# MCU1.net
KiCad netlist of a schematic drawn in Altium Designer
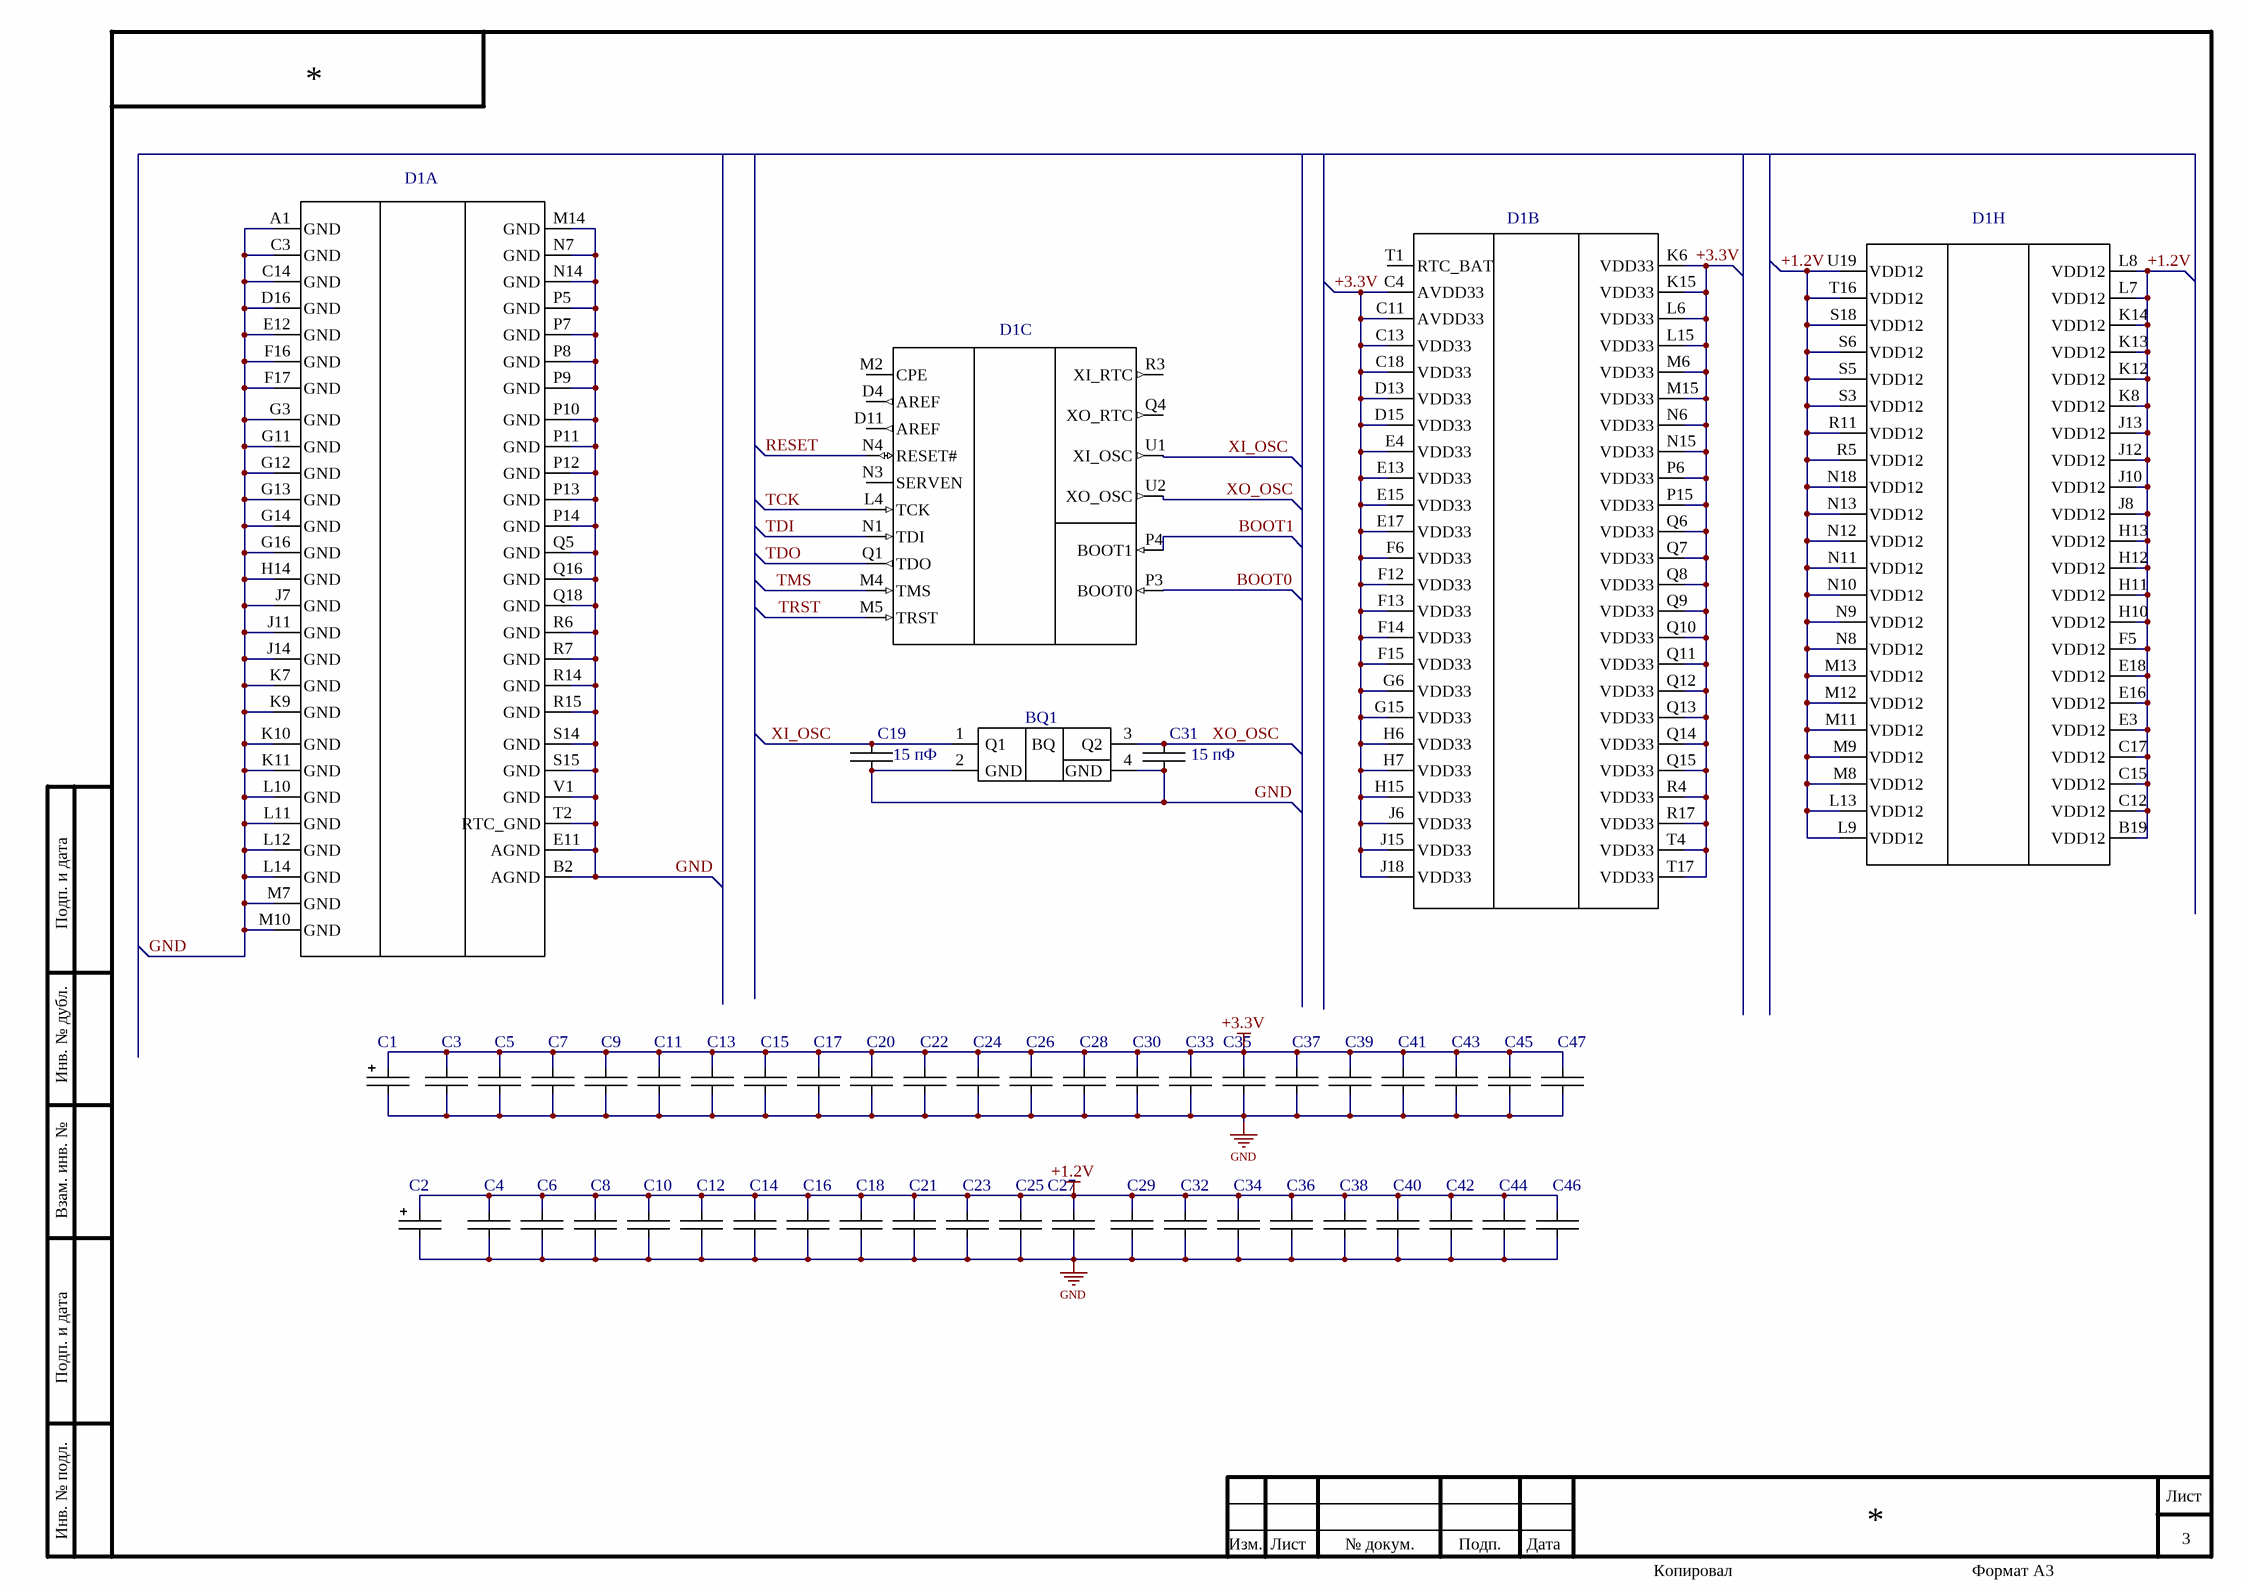
[diagram p0: MCU1.SchDoc]

(export (version "E")
  (design (tool "Eeschema 10.0.6"))
  (components
    (comp (ref "BQ1")
      (value "Резонатор РК463-5ДС-16,0М")
      (footprint "RK463_BQ_RK-463(Primary)")
      (description "Кварцевый резонатор")
      (libsource (lib "Блок вычислительный") (part "РК463-5ДС"))
    )
    (comp (ref "C1")
      (value "22 мкФ")
      (footprint "К53-67")
      (description "Оксидно-полупроводниковый танталовый чип-конденсатор серии К53-68")
      (fields (field (name "PARTNUMBER") "К53-67 \"*\"-* В-* мкФ ±*%"))
      (libsource (lib "Блок вычислительный") (part "К53-67"))
    )
    (comp (ref "C2")
      (value "22 мкФ")
      (footprint "К53-67")
      (description "Оксидно-полупроводниковый танталовый чип-конденсатор серии К53-68")
      (fields (field (name "PARTNUMBER") "К53-67 \"*\"-* В-* мкФ ±*%"))
      (libsource (lib "Блок вычислительный") (part "К53-67"))
    )
    (comp (ref "C3")
      (value "0.1 мкФ")
      (footprint "блок вычислительный_v1:C0805")
      (description "Керамический чип-конденсатор серии К10-69")
      (fields (field (name "PARTNUMBER") "К10-69в-*-* В- * ± *% *"))
      (libsource (lib "Блок вычислительный") (part "К10-69_0.1mk"))
    )
    (comp (ref "C4")
      (value "0.1 мкФ")
      (footprint "блок вычислительный_v1:C0805")
      (description "Керамический чип-конденсатор серии К10-69")
      (fields (field (name "PARTNUMBER") "К10-69в-*-* В- * ± *% *"))
      (libsource (lib "Блок вычислительный") (part "К10-69_0.1mk"))
    )
    (comp (ref "C5")
      (value "0.1 мкФ")
      (footprint "блок вычислительный_v1:C0805")
      (description "Керамический чип-конденсатор серии К10-69")
      (fields (field (name "PARTNUMBER") "К10-69в-*-* В- * ± *% *"))
      (libsource (lib "Блок вычислительный") (part "К10-69_0.1mk"))
    )
    (comp (ref "C6")
      (value "0.1 мкФ")
      (footprint "блок вычислительный_v1:C0805")
      (description "Керамический чип-конденсатор серии К10-69")
      (fields (field (name "PARTNUMBER") "К10-69в-*-* В- * ± *% *"))
      (libsource (lib "Блок вычислительный") (part "К10-69_0.1mk"))
    )
    (comp (ref "C7")
      (value "0.1 мкФ")
      (footprint "блок вычислительный_v1:C0805")
      (description "Керамический чип-конденсатор серии К10-69")
      (fields (field (name "PARTNUMBER") "К10-69в-*-* В- * ± *% *"))
      (libsource (lib "Блок вычислительный") (part "К10-69_0.1mk"))
    )
    (comp (ref "C8")
      (value "0.1 мкФ")
      (footprint "блок вычислительный_v1:C0805")
      (description "Керамический чип-конденсатор серии К10-69")
      (fields (field (name "PARTNUMBER") "К10-69в-*-* В- * ± *% *"))
      (libsource (lib "Блок вычислительный") (part "К10-69_0.1mk"))
    )
    (comp (ref "C9")
      (value "0.1 мкФ")
      (footprint "блок вычислительный_v1:C0805")
      (description "Керамический чип-конденсатор серии К10-69")
      (fields (field (name "PARTNUMBER") "К10-69в-*-* В- * ± *% *"))
      (libsource (lib "Блок вычислительный") (part "К10-69_0.1mk"))
    )
    (comp (ref "C10")
      (value "0.1 мкФ")
      (footprint "блок вычислительный_v1:C0805")
      (description "Керамический чип-конденсатор серии К10-69")
      (fields (field (name "PARTNUMBER") "К10-69в-*-* В- * ± *% *"))
      (libsource (lib "Блок вычислительный") (part "К10-69_0.1mk"))
    )
    (comp (ref "C11")
      (value "0.1 мкФ")
      (footprint "блок вычислительный_v1:C0805")
      (description "Керамический чип-конденсатор серии К10-69")
      (fields (field (name "PARTNUMBER") "К10-69в-*-* В- * ± *% *"))
      (libsource (lib "Блок вычислительный") (part "К10-69_0.1mk"))
    )
    (comp (ref "C12")
      (value "0.1 мкФ")
      (footprint "блок вычислительный_v1:C0805")
      (description "Керамический чип-конденсатор серии К10-69")
      (fields (field (name "PARTNUMBER") "К10-69в-*-* В- * ± *% *"))
      (libsource (lib "Блок вычислительный") (part "К10-69_0.1mk"))
    )
    (comp (ref "C13")
      (value "0.1 мкФ")
      (footprint "блок вычислительный_v1:C0805")
      (description "Керамический чип-конденсатор серии К10-69")
      (fields (field (name "PARTNUMBER") "К10-69в-*-* В- * ± *% *"))
      (libsource (lib "Блок вычислительный") (part "К10-69_0.1mk"))
    )
    (comp (ref "C14")
      (value "0.1 мкФ")
      (footprint "блок вычислительный_v1:C0805")
      (description "Керамический чип-конденсатор серии К10-69")
      (fields (field (name "PARTNUMBER") "К10-69в-*-* В- * ± *% *"))
      (libsource (lib "Блок вычислительный") (part "К10-69_0.1mk"))
    )
    (comp (ref "C15")
      (value "0.1 мкФ")
      (footprint "блок вычислительный_v1:C0805")
      (description "Керамический чип-конденсатор серии К10-69")
      (fields (field (name "PARTNUMBER") "К10-69в-*-* В- * ± *% *"))
      (libsource (lib "Блок вычислительный") (part "К10-69_0.1mk"))
    )
    (comp (ref "C16")
      (value "0.1 мкФ")
      (footprint "блок вычислительный_v1:C0805")
      (description "Керамический чип-конденсатор серии К10-69")
      (fields (field (name "PARTNUMBER") "К10-69в-*-* В- * ± *% *"))
      (libsource (lib "Блок вычислительный") (part "К10-69_0.1mk"))
    )
    (comp (ref "C17")
      (value "0.1 мкФ")
      (footprint "блок вычислительный_v1:C0805")
      (description "Керамический чип-конденсатор серии К10-69")
      (fields (field (name "PARTNUMBER") "К10-69в-*-* В- * ± *% *"))
      (libsource (lib "Блок вычислительный") (part "К10-69_0.1mk"))
    )
    (comp (ref "C18")
      (value "0.1 мкФ")
      (footprint "блок вычислительный_v1:C0805")
      (description "Керамический чип-конденсатор серии К10-69")
      (fields (field (name "PARTNUMBER") "К10-69в-*-* В- * ± *% *"))
      (libsource (lib "Блок вычислительный") (part "К10-69_0.1mk"))
    )
    (comp (ref "C19")
      (value "15 пФ")
      (footprint "блок вычислительный_v1:C0805")
      (description "Конденсатор неполярный")
      (libsource (lib "Блок вычислительный") (part "К10-69в_15p"))
    )
    (comp (ref "C20")
      (value "0.1 мкФ")
      (footprint "блок вычислительный_v1:C0805")
      (description "Керамический чип-конденсатор серии К10-69")
      (fields (field (name "PARTNUMBER") "К10-69в-*-* В- * ± *% *"))
      (libsource (lib "Блок вычислительный") (part "К10-69_0.1mk"))
    )
    (comp (ref "C21")
      (value "0.1 мкФ")
      (footprint "блок вычислительный_v1:C0805")
      (description "Керамический чип-конденсатор серии К10-69")
      (fields (field (name "PARTNUMBER") "К10-69в-*-* В- * ± *% *"))
      (libsource (lib "Блок вычислительный") (part "К10-69_0.1mk"))
    )
    (comp (ref "C22")
      (value "0.1 мкФ")
      (footprint "блок вычислительный_v1:C0805")
      (description "Керамический чип-конденсатор серии К10-69")
      (fields (field (name "PARTNUMBER") "К10-69в-*-* В- * ± *% *"))
      (libsource (lib "Блок вычислительный") (part "К10-69_0.1mk"))
    )
    (comp (ref "C23")
      (value "0.1 мкФ")
      (footprint "блок вычислительный_v1:C0805")
      (description "Керамический чип-конденсатор серии К10-69")
      (fields (field (name "PARTNUMBER") "К10-69в-*-* В- * ± *% *"))
      (libsource (lib "Блок вычислительный") (part "К10-69_0.1mk"))
    )
    (comp (ref "C24")
      (value "0.1 мкФ")
      (footprint "блок вычислительный_v1:C0805")
      (description "Керамический чип-конденсатор серии К10-69")
      (fields (field (name "PARTNUMBER") "К10-69в-*-* В- * ± *% *"))
      (libsource (lib "Блок вычислительный") (part "К10-69_0.1mk"))
    )
    (comp (ref "C25")
      (value "0.1 мкФ")
      (footprint "блок вычислительный_v1:C0805")
      (description "Керамический чип-конденсатор серии К10-69")
      (fields (field (name "PARTNUMBER") "К10-69в-*-* В- * ± *% *"))
      (libsource (lib "Блок вычислительный") (part "К10-69_0.1mk"))
    )
    (comp (ref "C26")
      (value "0.1 мкФ")
      (footprint "блок вычислительный_v1:C0805")
      (description "Керамический чип-конденсатор серии К10-69")
      (fields (field (name "PARTNUMBER") "К10-69в-*-* В- * ± *% *"))
      (libsource (lib "Блок вычислительный") (part "К10-69_0.1mk"))
    )
    (comp (ref "C27")
      (value "0.1 мкФ")
      (footprint "блок вычислительный_v1:C0805")
      (description "Керамический чип-конденсатор серии К10-69")
      (fields (field (name "PARTNUMBER") "К10-69в-*-* В- * ± *% *"))
      (libsource (lib "Блок вычислительный") (part "К10-69_0.1mk"))
    )
    (comp (ref "C28")
      (value "0.1 мкФ")
      (footprint "блок вычислительный_v1:C0805")
      (description "Керамический чип-конденсатор серии К10-69")
      (fields (field (name "PARTNUMBER") "К10-69в-*-* В- * ± *% *"))
      (libsource (lib "Блок вычислительный") (part "К10-69_0.1mk"))
    )
    (comp (ref "C29")
      (value "0.1 мкФ")
      (footprint "блок вычислительный_v1:C0805")
      (description "Керамический чип-конденсатор серии К10-69")
      (fields (field (name "PARTNUMBER") "К10-69в-*-* В- * ± *% *"))
      (libsource (lib "Блок вычислительный") (part "К10-69_0.1mk"))
    )
    (comp (ref "C30")
      (value "0.1 мкФ")
      (footprint "блок вычислительный_v1:C0805")
      (description "Керамический чип-конденсатор серии К10-69")
      (fields (field (name "PARTNUMBER") "К10-69в-*-* В- * ± *% *"))
      (libsource (lib "Блок вычислительный") (part "К10-69_0.1mk"))
    )
    (comp (ref "C31")
      (value "15 пФ")
      (footprint "блок вычислительный_v1:C0805")
      (description "Конденсатор неполярный")
      (libsource (lib "Блок вычислительный") (part "К10-69в_15p"))
    )
    (comp (ref "C32")
      (value "0.1 мкФ")
      (footprint "блок вычислительный_v1:C0805")
      (description "Керамический чип-конденсатор серии К10-69")
      (fields (field (name "PARTNUMBER") "К10-69в-*-* В- * ± *% *"))
      (libsource (lib "Блок вычислительный") (part "К10-69_0.1mk"))
    )
    (comp (ref "C33")
      (value "0.1 мкФ")
      (footprint "блок вычислительный_v1:C0805")
      (description "Керамический чип-конденсатор серии К10-69")
      (fields (field (name "PARTNUMBER") "К10-69в-*-* В- * ± *% *"))
      (libsource (lib "Блок вычислительный") (part "К10-69_0.1mk"))
    )
    (comp (ref "C34")
      (value "0.1 мкФ")
      (footprint "блок вычислительный_v1:C0805")
      (description "Керамический чип-конденсатор серии К10-69")
      (fields (field (name "PARTNUMBER") "К10-69в-*-* В- * ± *% *"))
      (libsource (lib "Блок вычислительный") (part "К10-69_0.1mk"))
    )
    (comp (ref "C35")
      (value "0.1 мкФ")
      (footprint "блок вычислительный_v1:C0805")
      (description "Керамический чип-конденсатор серии К10-69")
      (fields (field (name "PARTNUMBER") "К10-69в-*-* В- * ± *% *"))
      (libsource (lib "Блок вычислительный") (part "К10-69_0.1mk"))
    )
    (comp (ref "C36")
      (value "0.1 мкФ")
      (footprint "блок вычислительный_v1:C0805")
      (description "Керамический чип-конденсатор серии К10-69")
      (fields (field (name "PARTNUMBER") "К10-69в-*-* В- * ± *% *"))
      (libsource (lib "Блок вычислительный") (part "К10-69_0.1mk"))
    )
    (comp (ref "C37")
      (value "0.1 мкФ")
      (footprint "блок вычислительный_v1:C0805")
      (description "Керамический чип-конденсатор серии К10-69")
      (fields (field (name "PARTNUMBER") "К10-69в-*-* В- * ± *% *"))
      (libsource (lib "Блок вычислительный") (part "К10-69_0.1mk"))
    )
    (comp (ref "C38")
      (value "0.1 мкФ")
      (footprint "блок вычислительный_v1:C0805")
      (description "Керамический чип-конденсатор серии К10-69")
      (fields (field (name "PARTNUMBER") "К10-69в-*-* В- * ± *% *"))
      (libsource (lib "Блок вычислительный") (part "К10-69_0.1mk"))
    )
    (comp (ref "C39")
      (value "0.1 мкФ")
      (footprint "блок вычислительный_v1:C0805")
      (description "Керамический чип-конденсатор серии К10-69")
      (fields (field (name "PARTNUMBER") "К10-69в-*-* В- * ± *% *"))
      (libsource (lib "Блок вычислительный") (part "К10-69_0.1mk"))
    )
    (comp (ref "C40")
      (value "0.1 мкФ")
      (footprint "блок вычислительный_v1:C0805")
      (description "Керамический чип-конденсатор серии К10-69")
      (fields (field (name "PARTNUMBER") "К10-69в-*-* В- * ± *% *"))
      (libsource (lib "Блок вычислительный") (part "К10-69_0.1mk"))
    )
    (comp (ref "C41")
      (value "0.1 мкФ")
      (footprint "блок вычислительный_v1:C0805")
      (description "Керамический чип-конденсатор серии К10-69")
      (fields (field (name "PARTNUMBER") "К10-69в-*-* В- * ± *% *"))
      (libsource (lib "Блок вычислительный") (part "К10-69_0.1mk"))
    )
    (comp (ref "C42")
      (value "0.1 мкФ")
      (footprint "блок вычислительный_v1:C0805")
      (description "Керамический чип-конденсатор серии К10-69")
      (fields (field (name "PARTNUMBER") "К10-69в-*-* В- * ± *% *"))
      (libsource (lib "Блок вычислительный") (part "К10-69_0.1mk"))
    )
    (comp (ref "C43")
      (value "0.1 мкФ")
      (footprint "блок вычислительный_v1:C0805")
      (description "Керамический чип-конденсатор серии К10-69")
      (fields (field (name "PARTNUMBER") "К10-69в-*-* В- * ± *% *"))
      (libsource (lib "Блок вычислительный") (part "К10-69_0.1mk"))
    )
    (comp (ref "C44")
      (value "0.1 мкФ")
      (footprint "блок вычислительный_v1:C0805")
      (description "Керамический чип-конденсатор серии К10-69")
      (fields (field (name "PARTNUMBER") "К10-69в-*-* В- * ± *% *"))
      (libsource (lib "Блок вычислительный") (part "К10-69_0.1mk"))
    )
    (comp (ref "C45")
      (value "0.1 мкФ")
      (footprint "блок вычислительный_v1:C0805")
      (description "Керамический чип-конденсатор серии К10-69")
      (fields (field (name "PARTNUMBER") "К10-69в-*-* В- * ± *% *"))
      (libsource (lib "Блок вычислительный") (part "К10-69_0.1mk"))
    )
    (comp (ref "C46")
      (value "0.1 мкФ")
      (footprint "блок вычислительный_v1:C0805")
      (description "Керамический чип-конденсатор серии К10-69")
      (fields (field (name "PARTNUMBER") "К10-69в-*-* В- * ± *% *"))
      (libsource (lib "Блок вычислительный") (part "К10-69_0.1mk"))
    )
    (comp (ref "C47")
      (value "0.1 мкФ")
      (footprint "блок вычислительный_v1:C0805")
      (description "Керамический чип-конденсатор серии К10-69")
      (fields (field (name "PARTNUMBER") "К10-69в-*-* В- * ± *% *"))
      (libsource (lib "Блок вычислительный") (part "К10-69_0.1mk"))
    )
    (comp (ref "D1")
      (value "1921ВК028")
      (footprint "BGA-400_21.0X21.0MM_LAYOUT20X20_P1.0MM")
      (description "МК 1921ВК028")
      (libsource (lib "Блок вычислительный") (part "1921ВК028"))
    )
  )
  (nets
    (net (code "1") (name "+1.2V") (class "Default")
      (node (ref "C10") (pin "1") (pinfunction "1_1") (pintype "passive"))
      (node (ref "C12") (pin "1") (pinfunction "1_1") (pintype "passive"))
      (node (ref "C14") (pin "1") (pinfunction "1_1") (pintype "passive"))
      (node (ref "C16") (pin "1") (pinfunction "1_1") (pintype "passive"))
      (node (ref "C18") (pin "1") (pinfunction "1_1") (pintype "passive"))
      (node (ref "C2") (pin "1") (pinfunction "1_1") (pintype "passive"))
      (node (ref "C21") (pin "1") (pinfunction "1_1") (pintype "passive"))
      (node (ref "C23") (pin "1") (pinfunction "1_1") (pintype "passive"))
      (node (ref "C25") (pin "1") (pinfunction "1_1") (pintype "passive"))
      (node (ref "C27") (pin "1") (pinfunction "1_1") (pintype "passive"))
      (node (ref "C29") (pin "1") (pinfunction "1_1") (pintype "passive"))
      (node (ref "C32") (pin "1") (pinfunction "1_1") (pintype "passive"))
      (node (ref "C34") (pin "1") (pinfunction "1_1") (pintype "passive"))
      (node (ref "C36") (pin "1") (pinfunction "1_1") (pintype "passive"))
      (node (ref "C38") (pin "1") (pinfunction "1_1") (pintype "passive"))
      (node (ref "C4") (pin "1") (pinfunction "1_1") (pintype "passive"))
      (node (ref "C40") (pin "1") (pinfunction "1_1") (pintype "passive"))
      (node (ref "C42") (pin "1") (pinfunction "1_1") (pintype "passive"))
      (node (ref "C44") (pin "1") (pinfunction "1_1") (pintype "passive"))
      (node (ref "C46") (pin "1") (pinfunction "1_1") (pintype "passive"))
      (node (ref "C6") (pin "1") (pinfunction "1_1") (pintype "passive"))
      (node (ref "C8") (pin "1") (pinfunction "1_1") (pintype "passive"))
      (node (ref "D1") (pin "B19") (pinfunction "VDD12_B19") (pintype "power_in"))
      (node (ref "D1") (pin "C12") (pinfunction "VDD12_C12") (pintype "power_in"))
      (node (ref "D1") (pin "C15") (pinfunction "VDD12_C15") (pintype "power_in"))
      (node (ref "D1") (pin "C17") (pinfunction "VDD12_C17") (pintype "power_in"))
      (node (ref "D1") (pin "E16") (pinfunction "VDD12_E16") (pintype "power_in"))
      (node (ref "D1") (pin "E18") (pinfunction "VDD12_E18") (pintype "power_in"))
      (node (ref "D1") (pin "E3") (pinfunction "VDD12_E3") (pintype "power_in"))
      (node (ref "D1") (pin "F5") (pinfunction "VDD12_F5") (pintype "power_in"))
      (node (ref "D1") (pin "H10") (pinfunction "VDD12_H10") (pintype "power_in"))
      (node (ref "D1") (pin "H11") (pinfunction "VDD12_H11") (pintype "power_in"))
      (node (ref "D1") (pin "H12") (pinfunction "VDD12_H12") (pintype "power_in"))
      (node (ref "D1") (pin "H13") (pinfunction "VDD12_H13") (pintype "power_in"))
      (node (ref "D1") (pin "J10") (pinfunction "VDD12_J10") (pintype "power_in"))
      (node (ref "D1") (pin "J12") (pinfunction "VDD12_J12") (pintype "power_in"))
      (node (ref "D1") (pin "J13") (pinfunction "VDD12_J13") (pintype "power_in"))
      (node (ref "D1") (pin "J8") (pinfunction "VDD12_J8") (pintype "power_in"))
      (node (ref "D1") (pin "K12") (pinfunction "VDD12_K12") (pintype "power_in"))
      (node (ref "D1") (pin "K13") (pinfunction "VDD12_K13") (pintype "power_in"))
      (node (ref "D1") (pin "K14") (pinfunction "VDD12_K14") (pintype "power_in"))
      (node (ref "D1") (pin "K8") (pinfunction "VDD12_K8") (pintype "power_in"))
      (node (ref "D1") (pin "L13") (pinfunction "VDD12_L13") (pintype "power_in"))
      (node (ref "D1") (pin "L7") (pinfunction "VDD12_L7") (pintype "power_in"))
      (node (ref "D1") (pin "L8") (pinfunction "VDD12_L8") (pintype "power_in"))
      (node (ref "D1") (pin "L9") (pinfunction "VDD12_L9") (pintype "power_in"))
      (node (ref "D1") (pin "M11") (pinfunction "VDD12_M11") (pintype "power_in"))
      (node (ref "D1") (pin "M12") (pinfunction "VDD12_M12") (pintype "power_in"))
      (node (ref "D1") (pin "M13") (pinfunction "VDD12_M13") (pintype "power_in"))
      (node (ref "D1") (pin "M8") (pinfunction "VDD12_M8") (pintype "power_in"))
      (node (ref "D1") (pin "M9") (pinfunction "VDD12_M9") (pintype "power_in"))
      (node (ref "D1") (pin "N10") (pinfunction "VDD12_N10") (pintype "power_in"))
      (node (ref "D1") (pin "N11") (pinfunction "VDD12_N11") (pintype "power_in"))
      (node (ref "D1") (pin "N12") (pinfunction "VDD12_N12") (pintype "power_in"))
      (node (ref "D1") (pin "N13") (pinfunction "VDD12_N13") (pintype "power_in"))
      (node (ref "D1") (pin "N18") (pinfunction "VDD12_N18") (pintype "power_in"))
      (node (ref "D1") (pin "N8") (pinfunction "VDD12_N8") (pintype "power_in"))
      (node (ref "D1") (pin "N9") (pinfunction "VDD12_N9") (pintype "power_in"))
      (node (ref "D1") (pin "R11") (pinfunction "VDD12_R11") (pintype "power_in"))
      (node (ref "D1") (pin "R5") (pinfunction "VDD12_R5") (pintype "power_in"))
      (node (ref "D1") (pin "S18") (pinfunction "VDD12_S18") (pintype "power_in"))
      (node (ref "D1") (pin "S3") (pinfunction "VDD12_S3") (pintype "power_in"))
      (node (ref "D1") (pin "S5") (pinfunction "VDD12_S5") (pintype "power_in"))
      (node (ref "D1") (pin "S6") (pinfunction "VDD12_S6") (pintype "power_in"))
      (node (ref "D1") (pin "T16") (pinfunction "VDD12_T16") (pintype "power_in"))
      (node (ref "D1") (pin "U19") (pinfunction "VDD12_U19") (pintype "power_in"))
    )
    (net (code "2") (name "+3.3V") (class "Default")
      (node (ref "C1") (pin "1") (pinfunction "1_1") (pintype "passive"))
      (node (ref "C11") (pin "1") (pinfunction "1_1") (pintype "passive"))
      (node (ref "C13") (pin "1") (pinfunction "1_1") (pintype "passive"))
      (node (ref "C15") (pin "1") (pinfunction "1_1") (pintype "passive"))
      (node (ref "C17") (pin "1") (pinfunction "1_1") (pintype "passive"))
      (node (ref "C20") (pin "1") (pinfunction "1_1") (pintype "passive"))
      (node (ref "C22") (pin "1") (pinfunction "1_1") (pintype "passive"))
      (node (ref "C24") (pin "1") (pinfunction "1_1") (pintype "passive"))
      (node (ref "C26") (pin "1") (pinfunction "1_1") (pintype "passive"))
      (node (ref "C28") (pin "1") (pinfunction "1_1") (pintype "passive"))
      (node (ref "C3") (pin "1") (pinfunction "1_1") (pintype "passive"))
      (node (ref "C30") (pin "1") (pinfunction "1_1") (pintype "passive"))
      (node (ref "C33") (pin "1") (pinfunction "1_1") (pintype "passive"))
      (node (ref "C35") (pin "1") (pinfunction "1_1") (pintype "passive"))
      (node (ref "C37") (pin "1") (pinfunction "1_1") (pintype "passive"))
      (node (ref "C39") (pin "1") (pinfunction "1_1") (pintype "passive"))
      (node (ref "C41") (pin "1") (pinfunction "1_1") (pintype "passive"))
      (node (ref "C43") (pin "1") (pinfunction "1_1") (pintype "passive"))
      (node (ref "C45") (pin "1") (pinfunction "1_1") (pintype "passive"))
      (node (ref "C47") (pin "1") (pinfunction "1_1") (pintype "passive"))
      (node (ref "C5") (pin "1") (pinfunction "1_1") (pintype "passive"))
      (node (ref "C7") (pin "1") (pinfunction "1_1") (pintype "passive"))
      (node (ref "C9") (pin "1") (pinfunction "1_1") (pintype "passive"))
      (node (ref "D1") (pin "C11") (pinfunction "AVDD33_C11") (pintype "power_in"))
      (node (ref "D1") (pin "C13") (pinfunction "VDD33_C13") (pintype "power_in"))
      (node (ref "D1") (pin "C18") (pinfunction "VDD33_C18") (pintype "power_in"))
      (node (ref "D1") (pin "C4") (pinfunction "AVDD33_C4") (pintype "power_in"))
      (node (ref "D1") (pin "D13") (pinfunction "VDD33_D13") (pintype "power_in"))
      (node (ref "D1") (pin "D15") (pinfunction "VDD33_D15") (pintype "power_in"))
      (node (ref "D1") (pin "E13") (pinfunction "VDD33_E13") (pintype "power_in"))
      (node (ref "D1") (pin "E15") (pinfunction "VDD33_E15") (pintype "power_in"))
      (node (ref "D1") (pin "E17") (pinfunction "VDD33_E17") (pintype "power_in"))
      (node (ref "D1") (pin "E4") (pinfunction "VDD33_E4") (pintype "power_in"))
      (node (ref "D1") (pin "F12") (pinfunction "VDD33_F12") (pintype "power_in"))
      (node (ref "D1") (pin "F13") (pinfunction "VDD33_F13") (pintype "power_in"))
      (node (ref "D1") (pin "F14") (pinfunction "VDD33_F14") (pintype "power_in"))
      (node (ref "D1") (pin "F15") (pinfunction "VDD33_F15") (pintype "power_in"))
      (node (ref "D1") (pin "F6") (pinfunction "VDD33_F6") (pintype "power_in"))
      (node (ref "D1") (pin "G15") (pinfunction "VDD33_G15") (pintype "power_in"))
      (node (ref "D1") (pin "G6") (pinfunction "VDD33_G6") (pintype "power_in"))
      (node (ref "D1") (pin "H15") (pinfunction "VDD33_H15") (pintype "power_in"))
      (node (ref "D1") (pin "H6") (pinfunction "VDD33_H6") (pintype "power_in"))
      (node (ref "D1") (pin "H7") (pinfunction "VDD33_H7") (pintype "power_in"))
      (node (ref "D1") (pin "J15") (pinfunction "VDD33_J15") (pintype "power_in"))
      (node (ref "D1") (pin "J18") (pinfunction "VDD33_J18") (pintype "power_in"))
      (node (ref "D1") (pin "J6") (pinfunction "VDD33_J6") (pintype "power_in"))
      (node (ref "D1") (pin "K15") (pinfunction "VDD33_K15") (pintype "power_in"))
      (node (ref "D1") (pin "K6") (pinfunction "VDD33_K6") (pintype "power_in"))
      (node (ref "D1") (pin "L15") (pinfunction "VDD33_L15") (pintype "power_in"))
      (node (ref "D1") (pin "L6") (pinfunction "VDD33_L6") (pintype "power_in"))
      (node (ref "D1") (pin "M15") (pinfunction "VDD33_M15") (pintype "power_in"))
      (node (ref "D1") (pin "M6") (pinfunction "VDD33_M6") (pintype "power_in"))
      (node (ref "D1") (pin "N15") (pinfunction "VDD33_N15") (pintype "power_in"))
      (node (ref "D1") (pin "N6") (pinfunction "VDD33_N6") (pintype "power_in"))
      (node (ref "D1") (pin "P15") (pinfunction "VDD33_P15") (pintype "power_in"))
      (node (ref "D1") (pin "P6") (pinfunction "VDD33_P6") (pintype "power_in"))
      (node (ref "D1") (pin "Q10") (pinfunction "VDD33_Q10") (pintype "power_in"))
      (node (ref "D1") (pin "Q11") (pinfunction "VDD33_Q11") (pintype "power_in"))
      (node (ref "D1") (pin "Q12") (pinfunction "VDD33_Q12") (pintype "power_in"))
      (node (ref "D1") (pin "Q13") (pinfunction "VDD33_Q13") (pintype "power_in"))
      (node (ref "D1") (pin "Q14") (pinfunction "VDD33_Q14") (pintype "power_in"))
      (node (ref "D1") (pin "Q15") (pinfunction "VDD33_Q15") (pintype "power_in"))
      (node (ref "D1") (pin "Q6") (pinfunction "VDD33_Q6") (pintype "power_in"))
      (node (ref "D1") (pin "Q7") (pinfunction "VDD33_Q7") (pintype "power_in"))
      (node (ref "D1") (pin "Q8") (pinfunction "VDD33_Q8") (pintype "power_in"))
      (node (ref "D1") (pin "Q9") (pinfunction "VDD33_Q9") (pintype "power_in"))
      (node (ref "D1") (pin "R17") (pinfunction "VDD33_R17") (pintype "power_in"))
      (node (ref "D1") (pin "R4") (pinfunction "VDD33_R4") (pintype "power_in"))
      (node (ref "D1") (pin "T17") (pinfunction "VDD33_T17") (pintype "power_in"))
      (node (ref "D1") (pin "T4") (pinfunction "VDD33_T4") (pintype "power_in"))
    )
    (net (code "3") (name "/BOOT0") (class "Default")
      (node (ref "D1") (pin "P3") (pinfunction "BOOT0_P3") (pintype "input"))
    )
    (net (code "4") (name "/BOOT1") (class "Default")
      (node (ref "D1") (pin "P4") (pinfunction "BOOT1_P4") (pintype "input"))
    )
    (net (code "5") (name "/RESET") (class "Default")
      (node (ref "D1") (pin "N4") (pinfunction "RESET#_N4") (pintype "bidirectional"))
    )
    (net (code "6") (name "/TCK") (class "Default")
      (node (ref "D1") (pin "L4") (pinfunction "TCK_L4") (pintype "input"))
    )
    (net (code "7") (name "/TDI") (class "Default")
      (node (ref "D1") (pin "N1") (pinfunction "TDI_N1") (pintype "input"))
    )
    (net (code "8") (name "/TDO") (class "Default")
      (node (ref "D1") (pin "Q1") (pinfunction "TDO_Q1") (pintype "output"))
    )
    (net (code "9") (name "/TMS") (class "Default")
      (node (ref "D1") (pin "M4") (pinfunction "TMS_M4") (pintype "input"))
    )
    (net (code "10") (name "/TRST") (class "Default")
      (node (ref "D1") (pin "M5") (pinfunction "TRST_M5") (pintype "input"))
    )
    (net (code "11") (name "/XI_OSC") (class "Default")
      (node (ref "BQ1") (pin "1") (pinfunction "Q1_1") (pintype "passive"))
      (node (ref "C19") (pin "1") (pinfunction "1_1") (pintype "passive"))
      (node (ref "D1") (pin "U1") (pinfunction "XI_OSC_U1") (pintype "output"))
    )
    (net (code "12") (name "/XO_OSC") (class "Default")
      (node (ref "BQ1") (pin "3") (pinfunction "Q2_3") (pintype "passive"))
      (node (ref "C31") (pin "1") (pinfunction "1_1") (pintype "passive"))
      (node (ref "D1") (pin "U2") (pinfunction "XO_OSC_U2") (pintype "output"))
    )
    (net (code "13") (name "GND") (class "Default")
      (node (ref "BQ1") (pin "2") (pinfunction "GND_2") (pintype "passive"))
      (node (ref "BQ1") (pin "4") (pinfunction "GND_4") (pintype "passive"))
      (node (ref "C1") (pin "2") (pinfunction "2_2") (pintype "passive"))
      (node (ref "C10") (pin "2") (pinfunction "2_2") (pintype "passive"))
      (node (ref "C11") (pin "2") (pinfunction "2_2") (pintype "passive"))
      (node (ref "C12") (pin "2") (pinfunction "2_2") (pintype "passive"))
      (node (ref "C13") (pin "2") (pinfunction "2_2") (pintype "passive"))
      (node (ref "C14") (pin "2") (pinfunction "2_2") (pintype "passive"))
      (node (ref "C15") (pin "2") (pinfunction "2_2") (pintype "passive"))
      (node (ref "C16") (pin "2") (pinfunction "2_2") (pintype "passive"))
      (node (ref "C17") (pin "2") (pinfunction "2_2") (pintype "passive"))
      (node (ref "C18") (pin "2") (pinfunction "2_2") (pintype "passive"))
      (node (ref "C19") (pin "2") (pinfunction "2_2") (pintype "passive"))
      (node (ref "C2") (pin "2") (pinfunction "2_2") (pintype "passive"))
      (node (ref "C20") (pin "2") (pinfunction "2_2") (pintype "passive"))
      (node (ref "C21") (pin "2") (pinfunction "2_2") (pintype "passive"))
      (node (ref "C22") (pin "2") (pinfunction "2_2") (pintype "passive"))
      (node (ref "C23") (pin "2") (pinfunction "2_2") (pintype "passive"))
      (node (ref "C24") (pin "2") (pinfunction "2_2") (pintype "passive"))
      (node (ref "C25") (pin "2") (pinfunction "2_2") (pintype "passive"))
      (node (ref "C26") (pin "2") (pinfunction "2_2") (pintype "passive"))
      (node (ref "C27") (pin "2") (pinfunction "2_2") (pintype "passive"))
      (node (ref "C28") (pin "2") (pinfunction "2_2") (pintype "passive"))
      (node (ref "C29") (pin "2") (pinfunction "2_2") (pintype "passive"))
      (node (ref "C3") (pin "2") (pinfunction "2_2") (pintype "passive"))
      (node (ref "C30") (pin "2") (pinfunction "2_2") (pintype "passive"))
      (node (ref "C31") (pin "2") (pinfunction "2_2") (pintype "passive"))
      (node (ref "C32") (pin "2") (pinfunction "2_2") (pintype "passive"))
      (node (ref "C33") (pin "2") (pinfunction "2_2") (pintype "passive"))
      (node (ref "C34") (pin "2") (pinfunction "2_2") (pintype "passive"))
      (node (ref "C35") (pin "2") (pinfunction "2_2") (pintype "passive"))
      (node (ref "C36") (pin "2") (pinfunction "2_2") (pintype "passive"))
      (node (ref "C37") (pin "2") (pinfunction "2_2") (pintype "passive"))
      (node (ref "C38") (pin "2") (pinfunction "2_2") (pintype "passive"))
      (node (ref "C39") (pin "2") (pinfunction "2_2") (pintype "passive"))
      (node (ref "C4") (pin "2") (pinfunction "2_2") (pintype "passive"))
      (node (ref "C40") (pin "2") (pinfunction "2_2") (pintype "passive"))
      (node (ref "C41") (pin "2") (pinfunction "2_2") (pintype "passive"))
      (node (ref "C42") (pin "2") (pinfunction "2_2") (pintype "passive"))
      (node (ref "C43") (pin "2") (pinfunction "2_2") (pintype "passive"))
      (node (ref "C44") (pin "2") (pinfunction "2_2") (pintype "passive"))
      (node (ref "C45") (pin "2") (pinfunction "2_2") (pintype "passive"))
      (node (ref "C46") (pin "2") (pinfunction "2_2") (pintype "passive"))
      (node (ref "C47") (pin "2") (pinfunction "2_2") (pintype "passive"))
      (node (ref "C5") (pin "2") (pinfunction "2_2") (pintype "passive"))
      (node (ref "C6") (pin "2") (pinfunction "2_2") (pintype "passive"))
      (node (ref "C7") (pin "2") (pinfunction "2_2") (pintype "passive"))
      (node (ref "C8") (pin "2") (pinfunction "2_2") (pintype "passive"))
      (node (ref "C9") (pin "2") (pinfunction "2_2") (pintype "passive"))
      (node (ref "D1") (pin "A1") (pinfunction "GND_A1") (pintype "power_in"))
      (node (ref "D1") (pin "B2") (pinfunction "AGND_B2") (pintype "power_in"))
      (node (ref "D1") (pin "C14") (pinfunction "GND_C14") (pintype "power_in"))
      (node (ref "D1") (pin "C3") (pinfunction "GND_C3") (pintype "power_in"))
      (node (ref "D1") (pin "D16") (pinfunction "GND_D16") (pintype "power_in"))
      (node (ref "D1") (pin "E11") (pinfunction "AGND_E11") (pintype "power_in"))
      (node (ref "D1") (pin "E12") (pinfunction "GND_E12") (pintype "power_in"))
      (node (ref "D1") (pin "F16") (pinfunction "GND_F16") (pintype "power_in"))
      (node (ref "D1") (pin "F17") (pinfunction "GND_F17") (pintype "power_in"))
      (node (ref "D1") (pin "G11") (pinfunction "GND_G11") (pintype "power_in"))
      (node (ref "D1") (pin "G12") (pinfunction "GND_G12") (pintype "power_in"))
      (node (ref "D1") (pin "G13") (pinfunction "GND_G13") (pintype "power_in"))
      (node (ref "D1") (pin "G14") (pinfunction "GND_G14") (pintype "power_in"))
      (node (ref "D1") (pin "G16") (pinfunction "GND_G16") (pintype "power_in"))
      (node (ref "D1") (pin "G3") (pinfunction "GND_G3") (pintype "power_in"))
      (node (ref "D1") (pin "H14") (pinfunction "GND_H14") (pintype "power_in"))
      (node (ref "D1") (pin "J11") (pinfunction "GND_J11") (pintype "power_in"))
      (node (ref "D1") (pin "J14") (pinfunction "GND_J14") (pintype "power_in"))
      (node (ref "D1") (pin "J7") (pinfunction "GND_J7") (pintype "power_in"))
      (node (ref "D1") (pin "K10") (pinfunction "GND_K10") (pintype "power_in"))
      (node (ref "D1") (pin "K11") (pinfunction "GND_K11") (pintype "power_in"))
      (node (ref "D1") (pin "K7") (pinfunction "GND_K7") (pintype "power_in"))
      (node (ref "D1") (pin "K9") (pinfunction "GND_K9") (pintype "power_in"))
      (node (ref "D1") (pin "L10") (pinfunction "GND_L10") (pintype "power_in"))
      (node (ref "D1") (pin "L11") (pinfunction "GND_L11") (pintype "power_in"))
      (node (ref "D1") (pin "L12") (pinfunction "GND_L12") (pintype "power_in"))
      (node (ref "D1") (pin "L14") (pinfunction "GND_L14") (pintype "power_in"))
      (node (ref "D1") (pin "M10") (pinfunction "GND_M10") (pintype "power_in"))
      (node (ref "D1") (pin "M14") (pinfunction "GND_M14") (pintype "power_in"))
      (node (ref "D1") (pin "M7") (pinfunction "GND_M7") (pintype "power_in"))
      (node (ref "D1") (pin "N14") (pinfunction "GND_N14") (pintype "power_in"))
      (node (ref "D1") (pin "N7") (pinfunction "GND_N7") (pintype "power_in"))
      (node (ref "D1") (pin "P10") (pinfunction "GND_P10") (pintype "power_in"))
      (node (ref "D1") (pin "P11") (pinfunction "GND_P11") (pintype "power_in"))
      (node (ref "D1") (pin "P12") (pinfunction "GND_P12") (pintype "power_in"))
      (node (ref "D1") (pin "P13") (pinfunction "GND_P13") (pintype "power_in"))
      (node (ref "D1") (pin "P14") (pinfunction "GND_P14") (pintype "power_in"))
      (node (ref "D1") (pin "P5") (pinfunction "GND_P5") (pintype "power_in"))
      (node (ref "D1") (pin "P7") (pinfunction "GND_P7") (pintype "power_in"))
      (node (ref "D1") (pin "P8") (pinfunction "GND_P8") (pintype "power_in"))
      (node (ref "D1") (pin "P9") (pinfunction "GND_P9") (pintype "power_in"))
      (node (ref "D1") (pin "Q16") (pinfunction "GND_Q16") (pintype "power_in"))
      (node (ref "D1") (pin "Q18") (pinfunction "GND_Q18") (pintype "power_in"))
      (node (ref "D1") (pin "Q5") (pinfunction "GND_Q5") (pintype "power_in"))
      (node (ref "D1") (pin "R14") (pinfunction "GND_R14") (pintype "power_in"))
      (node (ref "D1") (pin "R15") (pinfunction "GND_R15") (pintype "power_in"))
      (node (ref "D1") (pin "R6") (pinfunction "GND_R6") (pintype "power_in"))
      (node (ref "D1") (pin "R7") (pinfunction "GND_R7") (pintype "power_in"))
      (node (ref "D1") (pin "S14") (pinfunction "GND_S14") (pintype "power_in"))
      (node (ref "D1") (pin "S15") (pinfunction "GND_S15") (pintype "power_in"))
      (node (ref "D1") (pin "T2") (pinfunction "RTC_GND_T2") (pintype "power_in"))
      (node (ref "D1") (pin "V1") (pinfunction "GND_V1") (pintype "power_in"))
    )
    (net (code "14") (name "unconnected-(D1B-RTC_BAT-PadT1)") (class "Default")
      (node (ref "D1") (pin "T1") (pinfunction "RTC_BAT_T1") (pintype "power_in"))
    )
    (net (code "15") (name "unconnected-(D1C-AREF-PadD4)") (class "Default")
      (node (ref "D1") (pin "D4") (pinfunction "AREF_D4") (pintype "output"))
    )
    (net (code "16") (name "unconnected-(D1C-AREF-PadD11)") (class "Default")
      (node (ref "D1") (pin "D11") (pinfunction "AREF_D11") (pintype "output"))
    )
    (net (code "17") (name "unconnected-(D1C-CPE-PadM2)") (class "Default")
      (node (ref "D1") (pin "M2") (pinfunction "CPE_M2") (pintype "input"))
    )
    (net (code "18") (name "unconnected-(D1C-SERVEN-PadN3)") (class "Default")
      (node (ref "D1") (pin "N3") (pinfunction "SERVEN_N3") (pintype "input"))
    )
    (net (code "19") (name "unconnected-(D1C-XI_RTC-PadR3)") (class "Default")
      (node (ref "D1") (pin "R3") (pinfunction "XI_RTC_R3") (pintype "output"))
    )
    (net (code "20") (name "unconnected-(D1C-XO_RTC-PadQ4)") (class "Default")
      (node (ref "D1") (pin "Q4") (pinfunction "XO_RTC_Q4") (pintype "output"))
    )
  )
)
